# zxld383-boost-driver-12mm-mk-3.net
KiCad netlist of a schematic drawn in EAGLE
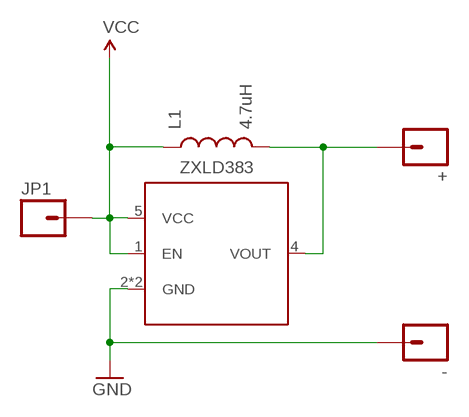
[diagram p0: schematic, sheet 1]

(export (version "E")
  (design (tool "Eeschema 10.0.6"))
  (components
    (comp (ref "+")
      (value "M01PTH-1.2MM")
      (footprint "eagle-import:1X01-1.2MM")
      (libsource (lib "eagle-import") (part "M01PTH-1.2MM"))
    )
    (comp (ref "-")
      (value "M01PTH-1.2MM-NS")
      (footprint "eagle-import:1X01-1.2MM-NS")
      (libsource (lib "eagle-import") (part "M01PTH-1.2MM-NS"))
    )
    (comp (ref "JP1")
      (value "M01NOT-A-VIA-NOPE")
      (footprint "eagle-import:1X01_NOSILK_NOSTOP")
      (libsource (lib "eagle-import") (part "M01NOT-A-VIA-NOPE"))
    )
    (comp (ref "L1")
      (value "4.7uH")
      (footprint "eagle-import:1007")
      (libsource (lib "eagle-import") (part "INDUCTOR1007"))
    )
    (comp (ref "ZXLD383")
      (value "ZXLD383")
      (footprint "eagle-import:TSOT-23-5")
      (libsource (lib "eagle-import") (part "ZXLD383"))
    )
  )
  (nets
    (net (code "1") (name "GND") (class "Default")
      (node (ref "-") (pin "P$1") (pinfunction "1_P$1") (pintype "passive"))
      (node (ref "ZXLD383") (pin "2") (pinfunction "GND_2") (pintype "bidirectional"))
      (node (ref "ZXLD383") (pin "3") (pinfunction "GND_3") (pintype "bidirectional"))
    )
    (net (code "2") (name "Net-(+-1)") (class "Default")
      (node (ref "+") (pin "P$1") (pinfunction "1_P$1") (pintype "passive"))
      (node (ref "L1") (pin "2") (pinfunction "2_2") (pintype "passive"))
      (node (ref "ZXLD383") (pin "4") (pinfunction "VOUT_4") (pintype "bidirectional"))
    )
    (net (code "3") (name "VCC") (class "Default")
      (node (ref "JP1") (pin "P$1") (pinfunction "1_P$1") (pintype "passive"))
      (node (ref "L1") (pin "1") (pinfunction "1_1") (pintype "passive"))
      (node (ref "ZXLD383") (pin "1") (pinfunction "EN_1") (pintype "bidirectional"))
      (node (ref "ZXLD383") (pin "5") (pinfunction "VCC_5") (pintype "bidirectional"))
    )
  )
)
